# Sheet2.net
KiCad netlist of a schematic drawn in Altium Designer
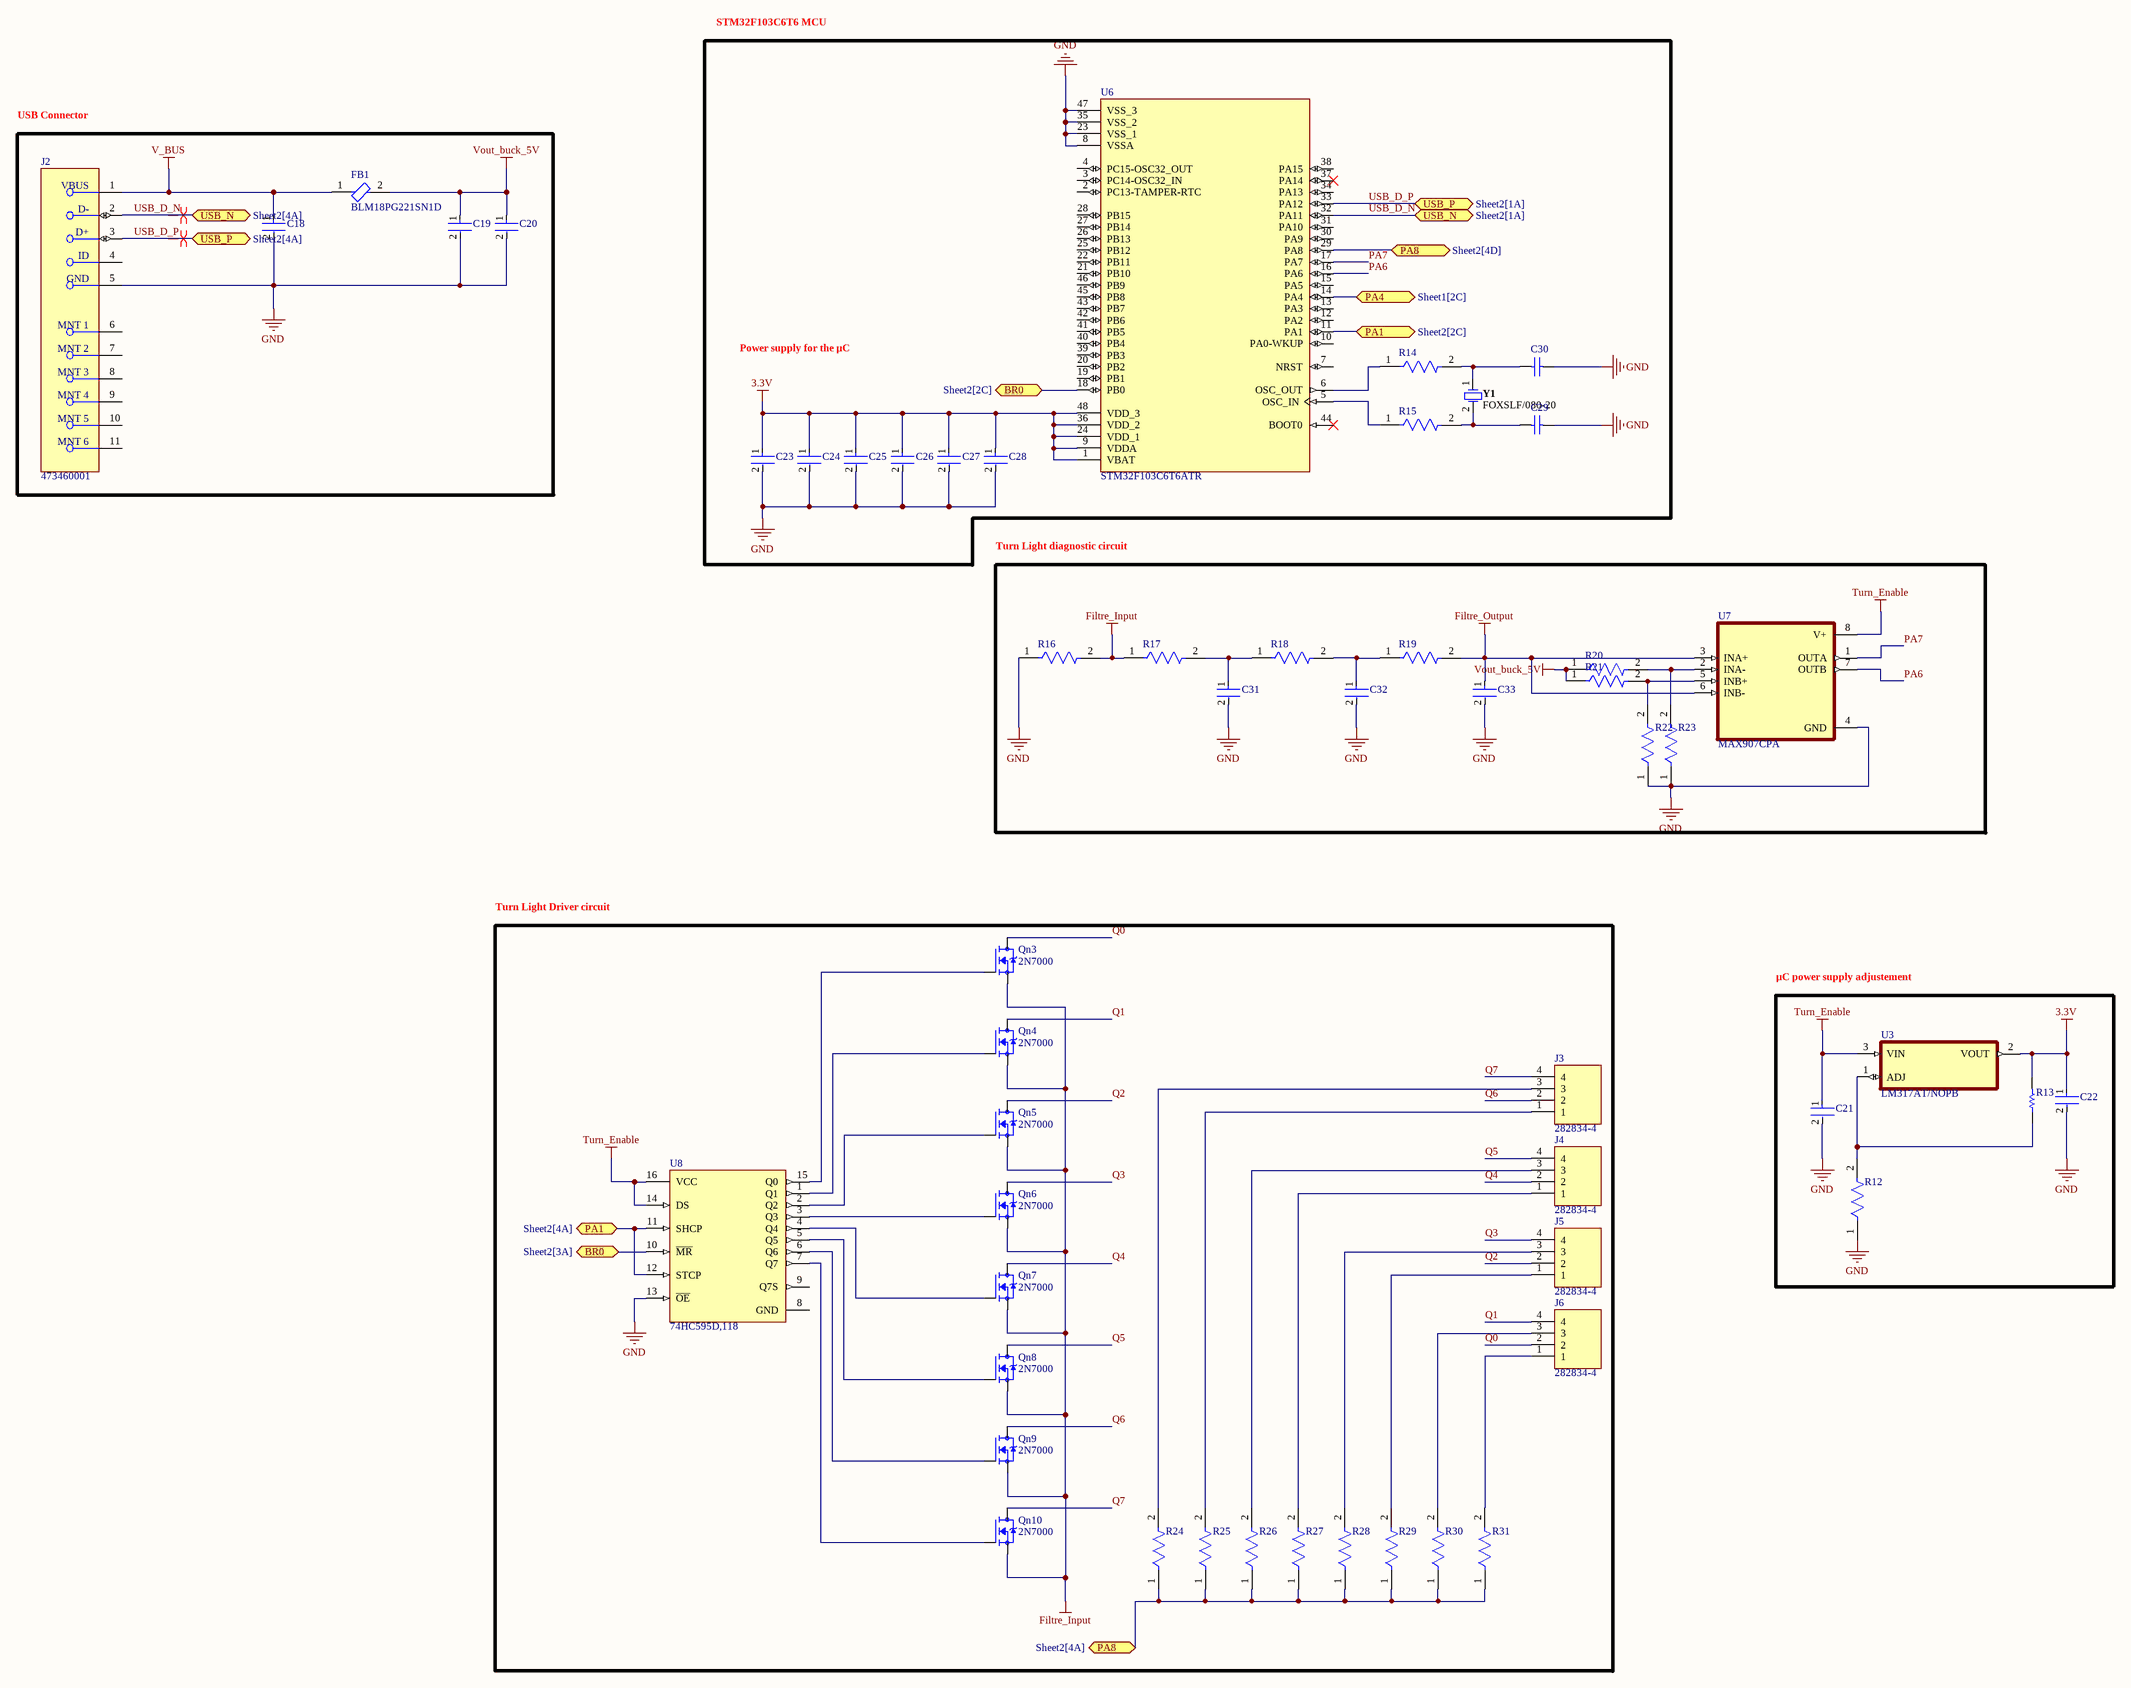
[diagram p0: Sheet2.SchDoc]

(export (version "E")
  (design (tool "Eeschema 10.0.6"))
  (components
    (comp (ref "C18")
      (value "06035C103KAT2A")
      (footprint "FP-0603-L_1_6_0_15-W_0_81-MFG")
      (description "General Purpose Ceramic Capacitor, 0603, 10nF, 10%, X7R, 15%, 50V")
      (fields (field (name "VOLTAGE") "50V") (field (name "TOLERANCE") "10%"))
      (libsource (lib "Altium Content Vault") (part "02cd4be3c70576c341d710602a673aa"))
    )
    (comp (ref "C19")
      (value "C0402C104K8PACTU")
      (footprint "FP-C0402-BB-MFG")
      (description "CAP CER 0.1UF 10V X5R 0402")
      (fields (field (name "MANUFACTURER") "Kemet") (field (name "TOLERANCE") "0.1"))
      (libsource (lib "Altium Content Vault") (part "b4654b650e69147ec39a6b967a45e02"))
    )
    (comp (ref "C20")
      (value "GRM155R60J475ME47D")
      (footprint "FP-GRM155-0_1-IPC_B")
      (description "Chip Multilayer Ceramic Capacitors for General Purpose, 0402, 4.7uF, X5R, 15%, 20%, 6.3V")
      (fields (field (name "VOLTAGE") "6.3V") (field (name "TOLERANCE") "20%"))
      (libsource (lib "Altium Content Vault") (part "11868f565c42a9108669ba33697ecf6"))
    )
    (comp (ref "C21")
      (value "CGA2B3X7R1H104M050BB")
      (footprint "FP-CGA2B-MFG")
      (description "Cap Ceramic 100nF 50V X7R 20% Pad SMD 0402 +125°C Automotive T/R")
      (fields (field (name "TOLERANCE") "20%"))
      (libsource (lib "Altium Content Vault") (part "b4654b650e69147ec39a6b967a45e02"))
    )
    (comp (ref "C22")
      (value "C0603C105K3PACTU")
      (footprint "FP-C0603C105K3PACTU-MFG")
      (description "CAP CER 1UF 25V X5R 0603")
      (fields (field (name "VOLTAGE") "25V") (field (name "TOLERANCE") "10%"))
      (libsource (lib "Altium Content Vault") (part "e9c51b7dd13d4faca003ae77663ab08"))
    )
    (comp (ref "C23")
      (value "GRM188R71A225KE15D")
      (footprint "FP-GRM188-0_1-e0_2_0_5-MFG")
      (description "Chip Multilayer Ceramic Capacitors for General Purpose, 0603, 2.2uF, X7R, 15%, 10%, 10V")
      (fields (field (name "VOLTAGE") "10V") (field (name "TOLERANCE") "10%"))
      (libsource (lib "Altium Content Vault") (part "11868f565c42a9108669ba33697ecf6"))
    )
    (comp (ref "C24")
      (value "C0402C104K8PACTU")
      (footprint "FP-C0402-BB-MFG")
      (description "CAP CER 0.1UF 10V X5R 0402")
      (fields (field (name "MANUFACTURER") "Kemet") (field (name "TOLERANCE") "0.1"))
      (libsource (lib "Altium Content Vault") (part "b4654b650e69147ec39a6b967a45e02"))
    )
    (comp (ref "C25")
      (value "C0402C104K8PACTU")
      (footprint "FP-C0402-BB-MFG")
      (description "CAP CER 0.1UF 10V X5R 0402")
      (fields (field (name "MANUFACTURER") "Kemet") (field (name "TOLERANCE") "0.1"))
      (libsource (lib "Altium Content Vault") (part "b4654b650e69147ec39a6b967a45e02"))
    )
    (comp (ref "C26")
      (value "C0402C104K8PACTU")
      (footprint "FP-C0402-BB-MFG")
      (description "CAP CER 0.1UF 10V X5R 0402")
      (fields (field (name "MANUFACTURER") "Kemet") (field (name "TOLERANCE") "0.1"))
      (libsource (lib "Altium Content Vault") (part "b4654b650e69147ec39a6b967a45e02"))
    )
    (comp (ref "C27")
      (value "C0402C104K8PACTU")
      (footprint "FP-C0402-BB-MFG")
      (description "CAP CER 0.1UF 10V X5R 0402")
      (fields (field (name "MANUFACTURER") "Kemet") (field (name "TOLERANCE") "0.1"))
      (libsource (lib "Altium Content Vault") (part "b4654b650e69147ec39a6b967a45e02"))
    )
    (comp (ref "C28")
      (value "C0402C104K8PACTU")
      (footprint "FP-C0402-BB-MFG")
      (description "CAP CER 0.1UF 10V X5R 0402")
      (fields (field (name "MANUFACTURER") "Kemet") (field (name "TOLERANCE") "0.1"))
      (libsource (lib "Altium Content Vault") (part "b4654b650e69147ec39a6b967a45e02"))
    )
    (comp (ref "C29")
      (value "C1608C0G1H220J080AA")
      (footprint "FP-C1608-080-0_1-IPC_B")
      (fields (field (name "PART NUMBER") "GRM1555C1H220JZ01D") (field (name "MANUFACTURER") "Murata"))
      (libsource (lib "Altium Content Vault") (part "CAP"))
    )
    (comp (ref "C30")
      (value "08052U220GAT2A")
      (footprint "CAPC2013X115X51NL20T26")
      (fields (field (name "PART NUMBER") "GRM1555C1H220JZ01D") (field (name "MANUFACTURER") "Murata"))
      (libsource (lib "Altium Content Vault") (part "CAP"))
    )
    (comp (ref "C31")
      (value "GRM188R60J106ME47D")
      (footprint "FP-GRM188-0_1-e0_2_0_55-IPC_A")
      (description "Chip Multilayer Ceramic Capacitors for General Purpose, 0603, 10uF, X5R, 15%, 20%, 6.3V")
      (fields (field (name "VOLTAGE") "6.3V") (field (name "TOLERANCE") "20%"))
      (libsource (lib "Altium Content Vault") (part "02cd4be3c70576c341d710602a673aa"))
    )
    (comp (ref "C32")
      (value "GRM188R60J106ME47D")
      (footprint "FP-GRM188-0_1-e0_2_0_55-IPC_A")
      (description "Chip Multilayer Ceramic Capacitors for General Purpose, 0603, 10uF, X5R, 15%, 20%, 6.3V")
      (fields (field (name "VOLTAGE") "6.3V") (field (name "TOLERANCE") "20%"))
      (libsource (lib "Altium Content Vault") (part "02cd4be3c70576c341d710602a673aa"))
    )
    (comp (ref "C33")
      (value "GRM188R60J106ME47D")
      (footprint "FP-GRM188-0_1-e0_2_0_55-IPC_A")
      (description "Chip Multilayer Ceramic Capacitors for General Purpose, 0603, 10uF, X5R, 15%, 20%, 6.3V")
      (fields (field (name "VOLTAGE") "6.3V") (field (name "TOLERANCE") "20%"))
      (libsource (lib "Altium Content Vault") (part "02cd4be3c70576c341d710602a673aa"))
    )
    (comp (ref "FB1")
      (value "BLM18PG221SN1D")
      (footprint "FP-BLM18-0_15-t0_8-IPC_B")
      (description "Chip Ferrite Bead, 0603, 220Ω @ 100MHz, 0.1Ω, 25%, 1.4A")
      (fields (field (name "TOLERANCE") "25%"))
      (libsource (lib "Altium Content Vault") (part "5f30dd21d616792df468990f7003faa"))
    )
    (comp (ref "J2")
      (value "473460001")
      (footprint "FP-473460001-MFG")
      (description "CONN RCPT USB2.0 MICRO B SMD R/A")
      (fields
        (field (name "OCTOPART") "https://octopart.com/47346-0001-molex-7164928")
        (field (name "MANUFACTURER") "Molex")
      )
      (libsource (lib "Altium Content Vault") (part "53ae1f1d9b557310b43ca686e5bb76a"))
    )
    (comp (ref "J3")
      (value "282834-4")
      (footprint "TE_282834-4")
      (description "4 Position Wire to Board Terminal Block Horizontal with Board 0.100 (2.54mm) Through Hole")
      (fields (field (name "MF") "TE Connectivity"))
      (libsource (lib "282834-4") (part "282834-4"))
    )
    (comp (ref "J4")
      (value "282834-4")
      (footprint "TE_282834-4")
      (description "4 Position Wire to Board Terminal Block Horizontal with Board 0.100 (2.54mm) Through Hole")
      (fields (field (name "MF") "TE Connectivity"))
      (libsource (lib "282834-4") (part "282834-4"))
    )
    (comp (ref "J5")
      (value "282834-4")
      (footprint "TE_282834-4")
      (description "4 Position Wire to Board Terminal Block Horizontal with Board 0.100 (2.54mm) Through Hole")
      (fields (field (name "MF") "TE Connectivity"))
      (libsource (lib "282834-4") (part "282834-4"))
    )
    (comp (ref "J6")
      (value "282834-4")
      (footprint "TE_282834-4")
      (description "4 Position Wire to Board Terminal Block Horizontal with Board 0.100 (2.54mm) Through Hole")
      (fields (field (name "MF") "TE Connectivity"))
      (libsource (lib "282834-4") (part "282834-4"))
    )
    (comp (ref "Qn3")
      (value "2N7000")
      (footprint "TO92-")
      (description "N-Channel 60 V 350mA (Tc) 1W (Tc) Through Hole TO-92-3")
      (fields (field (name "MF") "STMicroelectronics"))
      (libsource (lib "2N7000") (part "2N7000"))
    )
    (comp (ref "Qn4")
      (value "2N7000")
      (footprint "TO92-")
      (description "N-Channel 60 V 350mA (Tc) 1W (Tc) Through Hole TO-92-3")
      (fields (field (name "MF") "STMicroelectronics"))
      (libsource (lib "2N7000") (part "2N7000"))
    )
    (comp (ref "Qn5")
      (value "2N7000")
      (footprint "TO92-")
      (description "N-Channel 60 V 350mA (Tc) 1W (Tc) Through Hole TO-92-3")
      (fields (field (name "MF") "STMicroelectronics"))
      (libsource (lib "2N7000") (part "2N7000"))
    )
    (comp (ref "Qn6")
      (value "2N7000")
      (footprint "TO92-")
      (description "N-Channel 60 V 350mA (Tc) 1W (Tc) Through Hole TO-92-3")
      (fields (field (name "MF") "STMicroelectronics"))
      (libsource (lib "2N7000") (part "2N7000"))
    )
    (comp (ref "Qn7")
      (value "2N7000")
      (footprint "TO92-")
      (description "N-Channel 60 V 350mA (Tc) 1W (Tc) Through Hole TO-92-3")
      (fields (field (name "MF") "STMicroelectronics"))
      (libsource (lib "2N7000") (part "2N7000"))
    )
    (comp (ref "Qn8")
      (value "2N7000")
      (footprint "TO92-")
      (description "N-Channel 60 V 350mA (Tc) 1W (Tc) Through Hole TO-92-3")
      (fields (field (name "MF") "STMicroelectronics"))
      (libsource (lib "2N7000") (part "2N7000"))
    )
    (comp (ref "Qn9")
      (value "2N7000")
      (footprint "TO92-")
      (description "N-Channel 60 V 350mA (Tc) 1W (Tc) Through Hole TO-92-3")
      (fields (field (name "MF") "STMicroelectronics"))
      (libsource (lib "2N7000") (part "2N7000"))
    )
    (comp (ref "Qn10")
      (value "2N7000")
      (footprint "TO92-")
      (description "N-Channel 60 V 350mA (Tc) 1W (Tc) Through Hole TO-92-3")
      (fields (field (name "MF") "STMicroelectronics"))
      (libsource (lib "2N7000") (part "2N7000"))
    )
    (comp (ref "R12")
      (value "CRCW0603390RFKEA")
      (footprint "FP-CRCW0603-e3-IPC_B")
      (description "RES Thick Film, 390Ω, 1%, 0.1W, 100ppm/°C, 0603")
      (fields (field (name "TOLERANCE") "1%"))
      (libsource (lib "Altium Content Vault") (part "1029c3af85768c4190bb7ad29bc67b5"))
    )
    (comp (ref "R13")
      (value "CRCW0402240RFKED")
      (footprint "RESC1005X40X25ML05T05")
      (fields (field (name "MANUFACTURER") "Vishay Dale"))
      (libsource (lib "Altium Content Vault") (part "RES"))
    )
    (comp (ref "R14")
      (value "RCS06030000Z0EA")
      (footprint "FP-RCS0603-e3-MFG")
      (description "RES SMD 0 OHM JUMPER 1/4W 0603")
      (libsource (lib "Altium Content Vault") (part "1029c3af85768c4190bb7ad29bc67b5"))
    )
    (comp (ref "R15")
      (value "RCS06030000Z0EA")
      (footprint "FP-RCS0603-e3-MFG")
      (description "RES SMD 0 OHM JUMPER 1/4W 0603")
      (libsource (lib "Altium Content Vault") (part "1029c3af85768c4190bb7ad29bc67b5"))
    )
    (comp (ref "R16")
      (value "ERJ-2RKF10R0X")
      (footprint "FP-ERJ2RK-MFG")
      (description "RES SMD 10 OHM 1% 1/10W 0402")
      (fields
        (field (name "OCTOPART") "https://octopart.com/erj-2rkf10r0x-panasonic-55404982")
        (field (name "MANUFACTURER") "Panasonic")
      )
      (libsource (lib "Altium Content Vault") (part "1029c3af85768c4190bb7ad29bc67b5"))
    )
    (comp (ref "R17")
      (value "ERA-3AEB102V")
      (footprint "FP-ERA3A-IPC_C")
      (description "RES SMD 1K OHM 0.1% 1/10W 0603")
      (fields (field (name "TOLERANCE") "0.1%"))
      (libsource (lib "Altium Content Vault") (part "1029c3af85768c4190bb7ad29bc67b5"))
    )
    (comp (ref "R18")
      (value "ERA-3AEB102V")
      (footprint "FP-ERA3A-IPC_C")
      (description "RES SMD 1K OHM 0.1% 1/10W 0603")
      (fields (field (name "TOLERANCE") "0.1%"))
      (libsource (lib "Altium Content Vault") (part "1029c3af85768c4190bb7ad29bc67b5"))
    )
    (comp (ref "R19")
      (value "ERA-3AEB102V")
      (footprint "FP-ERA3A-IPC_C")
      (description "RES SMD 1K OHM 0.1% 1/10W 0603")
      (fields (field (name "TOLERANCE") "0.1%"))
      (libsource (lib "Altium Content Vault") (part "1029c3af85768c4190bb7ad29bc67b5"))
    )
    (comp (ref "R20")
      (value "ERA-3AEB102V")
      (footprint "FP-ERA3A-IPC_C")
      (description "RES SMD 1K OHM 0.1% 1/10W 0603")
      (fields (field (name "TOLERANCE") "0.1%"))
      (libsource (lib "Altium Content Vault") (part "1029c3af85768c4190bb7ad29bc67b5"))
    )
    (comp (ref "R21")
      (value "ERA-3AEB102V")
      (footprint "FP-ERA3A-IPC_C")
      (description "RES SMD 1K OHM 0.1% 1/10W 0603")
      (fields (field (name "TOLERANCE") "0.1%"))
      (libsource (lib "Altium Content Vault") (part "1029c3af85768c4190bb7ad29bc67b5"))
    )
    (comp (ref "R22")
      (value "CRCW060350R0FKEA")
      (footprint "FP-CRCW0603-e3-MFG")
      (description "RES Thick Film, 50Ω, 1%, 0.1W, 100ppm/°C, 0603")
      (fields (field (name "TOLERANCE") "1%"))
      (libsource (lib "Altium Content Vault") (part "1029c3af85768c4190bb7ad29bc67b5"))
    )
    (comp (ref "R23")
      (value "CRCW0402110RFKED")
      (footprint "FP-CRCW0402-e3-IPC_A")
      (description "RES Thick Film, 110Ω, 1%, 0.063W, 100ppm/°C, 0402")
      (fields (field (name "TOLERANCE") "1%"))
      (libsource (lib "Altium Content Vault") (part "1029c3af85768c4190bb7ad29bc67b5"))
    )
    (comp (ref "R24")
      (value "CRCW060350R0FKEA")
      (footprint "FP-CRCW0603-e3-MFG")
      (description "RES Thick Film, 50Ω, 1%, 0.1W, 100ppm/°C, 0603")
      (fields (field (name "TOLERANCE") "1%"))
      (libsource (lib "Altium Content Vault") (part "1029c3af85768c4190bb7ad29bc67b5"))
    )
    (comp (ref "R25")
      (value "CRCW060350R0FKEA")
      (footprint "FP-CRCW0603-e3-MFG")
      (description "RES Thick Film, 50Ω, 1%, 0.1W, 100ppm/°C, 0603")
      (fields (field (name "TOLERANCE") "1%"))
      (libsource (lib "Altium Content Vault") (part "1029c3af85768c4190bb7ad29bc67b5"))
    )
    (comp (ref "R26")
      (value "CRCW060350R0FKEA")
      (footprint "FP-CRCW0603-e3-MFG")
      (description "RES Thick Film, 50Ω, 1%, 0.1W, 100ppm/°C, 0603")
      (fields (field (name "TOLERANCE") "1%"))
      (libsource (lib "Altium Content Vault") (part "1029c3af85768c4190bb7ad29bc67b5"))
    )
    (comp (ref "R27")
      (value "CRCW060350R0FKEA")
      (footprint "FP-CRCW0603-e3-MFG")
      (description "RES Thick Film, 50Ω, 1%, 0.1W, 100ppm/°C, 0603")
      (fields (field (name "TOLERANCE") "1%"))
      (libsource (lib "Altium Content Vault") (part "1029c3af85768c4190bb7ad29bc67b5"))
    )
    (comp (ref "R28")
      (value "CRCW060350R0FKEA")
      (footprint "FP-CRCW0603-e3-MFG")
      (description "RES Thick Film, 50Ω, 1%, 0.1W, 100ppm/°C, 0603")
      (fields (field (name "TOLERANCE") "1%"))
      (libsource (lib "Altium Content Vault") (part "1029c3af85768c4190bb7ad29bc67b5"))
    )
    (comp (ref "R29")
      (value "CRCW060350R0FKEA")
      (footprint "FP-CRCW0603-e3-MFG")
      (description "RES Thick Film, 50Ω, 1%, 0.1W, 100ppm/°C, 0603")
      (fields (field (name "TOLERANCE") "1%"))
      (libsource (lib "Altium Content Vault") (part "1029c3af85768c4190bb7ad29bc67b5"))
    )
    (comp (ref "R30")
      (value "CRCW060350R0FKEA")
      (footprint "FP-CRCW0603-e3-MFG")
      (description "RES Thick Film, 50Ω, 1%, 0.1W, 100ppm/°C, 0603")
      (fields (field (name "TOLERANCE") "1%"))
      (libsource (lib "Altium Content Vault") (part "1029c3af85768c4190bb7ad29bc67b5"))
    )
    (comp (ref "R31")
      (value "CRCW060350R0FKEA")
      (footprint "FP-CRCW0603-e3-MFG")
      (description "RES Thick Film, 50Ω, 1%, 0.1W, 100ppm/°C, 0603")
      (fields (field (name "TOLERANCE") "1%"))
      (libsource (lib "Altium Content Vault") (part "1029c3af85768c4190bb7ad29bc67b5"))
    )
    (comp (ref "U3")
      (value "LM317AT/NOPB")
      (footprint "TO254P1054X470X1955-3")
      (description "1.5-A, 40-V, adjustable linear voltage regulator with high-accuracy 3-TO-220 -40 to 125")
      (fields (field (name "MP") "LM317AT") (field (name "MF") "Texas Instruments"))
      (libsource (lib "LM317AT_NOPB") (part "LM317AT/NOPB"))
    )
    (comp (ref "U6")
      (value "STM32F103C6T6ATR")
      (footprint "QFP50P900X900X160-48N")
      (description "ARMÂ® CortexÂ®-M3 STM32F1 Microcontroller IC 32-Bit 72MHz 32KB (32K x 8) FLASH")
      (fields (field (name "MF") "STMicroelectronics"))
      (libsource (lib "STM32F103C6T6ATR") (part "STM32F103C6T6ATR"))
    )
    (comp (ref "U7")
      (value "MAX907CPA")
      (footprint "DIP794W47P254L991H457Q8")
      (description "Comparator General Purpose TTL 8-PDIP")
      (fields (field (name "MF") "Maxim Integrated"))
      (libsource (lib "MAX907CPA") (part "MAX907CPA"))
    )
    (comp (ref "U8")
      (value "74HC595D,118")
      (footprint "FP-SOT109-1-IPC_C")
      (description "IC SHIFT REGISTER 8BIT 16SOIC")
      (libsource (lib "Altium Content Vault") (part "7b153f231cfcc3ac06dee253bd56617"))
    )
    (comp (ref "Y1")
      (value "FOXSLF/080-20")
      (footprint "FOX-FOXSLF080-20")
      (description "Resistance Weld Thru-Hole Crystal, 8 MHz, -20 to 70 degC, 2-Pin THD, RoHS, Bulk")
      (libsource (lib "Altium Content Vault") (part "XTAL-1-2-2"))
    )
  )
  (nets
    (net (code "1") (name "/BR0") (class "Default")
      (node (ref "U6") (pin "18") (pinfunction "PB0_18") (pintype "bidirectional"))
      (node (ref "U8") (pin "10") (pinfunction "~{MR}_10") (pintype "input"))
    )
    (net (code "2") (name "/PA1") (class "Default")
      (node (ref "U6") (pin "11") (pinfunction "PA1_11") (pintype "bidirectional"))
      (node (ref "U8") (pin "11") (pinfunction "SHCP_11") (pintype "input"))
      (node (ref "U8") (pin "12") (pinfunction "STCP_12") (pintype "input"))
    )
    (net (code "3") (name "/PA4") (class "Default")
      (node (ref "U6") (pin "14") (pinfunction "PA4_14") (pintype "bidirectional"))
    )
    (net (code "4") (name "/PA6") (class "Default")
      (node (ref "U6") (pin "16") (pinfunction "PA6_16") (pintype "bidirectional"))
      (node (ref "U7") (pin "7") (pinfunction "OUTB_7") (pintype "output"))
    )
    (net (code "5") (name "/PA7") (class "Default")
      (node (ref "U6") (pin "17") (pinfunction "PA7_17") (pintype "bidirectional"))
      (node (ref "U7") (pin "1") (pinfunction "OUTA_1") (pintype "output"))
    )
    (net (code "6") (name "/PA8") (class "Default")
      (node (ref "R24") (pin "1") (pinfunction "1_1") (pintype "passive"))
      (node (ref "R25") (pin "1") (pinfunction "1_1") (pintype "passive"))
      (node (ref "R26") (pin "1") (pinfunction "1_1") (pintype "passive"))
      (node (ref "R27") (pin "1") (pinfunction "1_1") (pintype "passive"))
      (node (ref "R28") (pin "1") (pinfunction "1_1") (pintype "passive"))
      (node (ref "R29") (pin "1") (pinfunction "1_1") (pintype "passive"))
      (node (ref "R30") (pin "1") (pinfunction "1_1") (pintype "passive"))
      (node (ref "R31") (pin "1") (pinfunction "1_1") (pintype "passive"))
      (node (ref "U6") (pin "29") (pinfunction "PA8_29") (pintype "bidirectional"))
    )
    (net (code "7") (name "/Q0") (class "Default")
      (node (ref "J6") (pin "2") (pinfunction "2_2") (pintype "passive"))
      (node (ref "Qn3") (pin "1") (pinfunction "D_1") (pintype "passive"))
    )
    (net (code "8") (name "/Q1") (class "Default")
      (node (ref "J6") (pin "4") (pinfunction "4_4") (pintype "passive"))
      (node (ref "Qn4") (pin "1") (pinfunction "D_1") (pintype "passive"))
    )
    (net (code "9") (name "/Q2") (class "Default")
      (node (ref "J5") (pin "2") (pinfunction "2_2") (pintype "passive"))
      (node (ref "Qn5") (pin "1") (pinfunction "D_1") (pintype "passive"))
    )
    (net (code "10") (name "/Q3") (class "Default")
      (node (ref "J5") (pin "4") (pinfunction "4_4") (pintype "passive"))
      (node (ref "Qn6") (pin "1") (pinfunction "D_1") (pintype "passive"))
    )
    (net (code "11") (name "/Q4") (class "Default")
      (node (ref "J4") (pin "2") (pinfunction "2_2") (pintype "passive"))
      (node (ref "Qn7") (pin "1") (pinfunction "D_1") (pintype "passive"))
    )
    (net (code "12") (name "/Q5") (class "Default")
      (node (ref "J4") (pin "4") (pinfunction "4_4") (pintype "passive"))
      (node (ref "Qn8") (pin "1") (pinfunction "D_1") (pintype "passive"))
    )
    (net (code "13") (name "/Q6") (class "Default")
      (node (ref "J3") (pin "2") (pinfunction "2_2") (pintype "passive"))
      (node (ref "Qn9") (pin "1") (pinfunction "D_1") (pintype "passive"))
    )
    (net (code "14") (name "/Q7") (class "Default")
      (node (ref "J3") (pin "4") (pinfunction "4_4") (pintype "passive"))
      (node (ref "Qn10") (pin "1") (pinfunction "D_1") (pintype "passive"))
    )
    (net (code "15") (name "/USB_D_N") (class "Default")
      (node (ref "J2") (pin "2") (pinfunction "D-_2") (pintype "bidirectional"))
      (node (ref "U6") (pin "32") (pinfunction "PA11_32") (pintype "bidirectional"))
    )
    (net (code "16") (name "/USB_D_P") (class "Default")
      (node (ref "J2") (pin "3") (pinfunction "D+_3") (pintype "bidirectional"))
      (node (ref "U6") (pin "33") (pinfunction "PA12_33") (pintype "bidirectional"))
    )
    (net (code "17") (name "3.3V") (class "Default")
      (node (ref "C22") (pin "1") (pinfunction "1_1") (pintype "passive"))
      (node (ref "C23") (pin "1") (pinfunction "1_1") (pintype "passive"))
      (node (ref "C24") (pin "1") (pinfunction "1_1") (pintype "passive"))
      (node (ref "C25") (pin "1") (pinfunction "1_1") (pintype "passive"))
      (node (ref "C26") (pin "1") (pinfunction "1_1") (pintype "passive"))
      (node (ref "C27") (pin "1") (pinfunction "1_1") (pintype "passive"))
      (node (ref "C28") (pin "1") (pinfunction "1_1") (pintype "passive"))
      (node (ref "R13") (pin "2") (pinfunction "2_2") (pintype "passive"))
      (node (ref "U3") (pin "2") (pinfunction "VOUT_2") (pintype "output"))
      (node (ref "U6") (pin "1") (pinfunction "VBAT_1") (pintype "power_in"))
      (node (ref "U6") (pin "24") (pinfunction "VDD_1_24") (pintype "power_in"))
      (node (ref "U6") (pin "36") (pinfunction "VDD_2_36") (pintype "power_in"))
      (node (ref "U6") (pin "48") (pinfunction "VDD_3_48") (pintype "power_in"))
      (node (ref "U6") (pin "9") (pinfunction "VDDA_9") (pintype "power_in"))
    )
    (net (code "18") (name "Filtre_Input") (class "Default")
      (node (ref "Qn10") (pin "3") (pinfunction "S_3") (pintype "passive"))
      (node (ref "Qn3") (pin "3") (pinfunction "S_3") (pintype "passive"))
      (node (ref "Qn4") (pin "3") (pinfunction "S_3") (pintype "passive"))
      (node (ref "Qn5") (pin "3") (pinfunction "S_3") (pintype "passive"))
      (node (ref "Qn6") (pin "3") (pinfunction "S_3") (pintype "passive"))
      (node (ref "Qn7") (pin "3") (pinfunction "S_3") (pintype "passive"))
      (node (ref "Qn8") (pin "3") (pinfunction "S_3") (pintype "passive"))
      (node (ref "Qn9") (pin "3") (pinfunction "S_3") (pintype "passive"))
      (node (ref "R16") (pin "2") (pinfunction "2_2") (pintype "passive"))
      (node (ref "R17") (pin "1") (pinfunction "1_1") (pintype "passive"))
    )
    (net (code "19") (name "Filtre_Output") (class "Default")
      (node (ref "C33") (pin "1") (pinfunction "1_1") (pintype "passive"))
      (node (ref "R19") (pin "2") (pinfunction "2_2") (pintype "passive"))
      (node (ref "U7") (pin "3") (pinfunction "INA+_3") (pintype "input"))
      (node (ref "U7") (pin "6") (pinfunction "INB-_6") (pintype "input"))
    )
    (net (code "20") (name "GND") (class "Default")
      (node (ref "C18") (pin "2") (pinfunction "2_2") (pintype "passive"))
      (node (ref "C19") (pin "2") (pinfunction "2_2") (pintype "passive"))
      (node (ref "C20") (pin "2") (pinfunction "2_2") (pintype "passive"))
      (node (ref "C21") (pin "2") (pinfunction "2_2") (pintype "passive"))
      (node (ref "C22") (pin "2") (pinfunction "2_2") (pintype "passive"))
      (node (ref "C23") (pin "2") (pinfunction "2_2") (pintype "passive"))
      (node (ref "C24") (pin "2") (pinfunction "2_2") (pintype "passive"))
      (node (ref "C25") (pin "2") (pinfunction "2_2") (pintype "passive"))
      (node (ref "C26") (pin "2") (pinfunction "2_2") (pintype "passive"))
      (node (ref "C27") (pin "2") (pinfunction "2_2") (pintype "passive"))
      (node (ref "C28") (pin "2") (pinfunction "2_2") (pintype "passive"))
      (node (ref "C29") (pin "1") (pinfunction "1_1") (pintype "passive"))
      (node (ref "C30") (pin "1") (pinfunction "1_1") (pintype "passive"))
      (node (ref "C31") (pin "2") (pinfunction "2_2") (pintype "passive"))
      (node (ref "C32") (pin "2") (pinfunction "2_2") (pintype "passive"))
      (node (ref "C33") (pin "2") (pinfunction "2_2") (pintype "passive"))
      (node (ref "J2") (pin "5") (pinfunction "GND_5") (pintype "power_in"))
      (node (ref "R12") (pin "1") (pinfunction "1_1") (pintype "passive"))
      (node (ref "R16") (pin "1") (pinfunction "1_1") (pintype "passive"))
      (node (ref "R22") (pin "1") (pinfunction "1_1") (pintype "passive"))
      (node (ref "R23") (pin "1") (pinfunction "1_1") (pintype "passive"))
      (node (ref "U6") (pin "23") (pinfunction "VSS_1_23") (pintype "power_in"))
      (node (ref "U6") (pin "35") (pinfunction "VSS_2_35") (pintype "power_in"))
      (node (ref "U6") (pin "47") (pinfunction "VSS_3_47") (pintype "power_in"))
      (node (ref "U6") (pin "8") (pinfunction "VSSA_8") (pintype "power_in"))
      (node (ref "U7") (pin "4") (pinfunction "GND_4") (pintype "power_in"))
      (node (ref "U8") (pin "13") (pinfunction "~{OE}_13") (pintype "input"))
    )
    (net (code "21") (name "Net-(C29-Pad2)") (class "Default")
      (node (ref "C29") (pin "2") (pinfunction "2_2") (pintype "passive"))
      (node (ref "R15") (pin "2") (pinfunction "2_2") (pintype "passive"))
      (node (ref "Y1") (pin "2") (pinfunction "2_2") (pintype "passive"))
    )
    (net (code "22") (name "Net-(C30-Pad2)") (class "Default")
      (node (ref "C30") (pin "2") (pinfunction "2_2") (pintype "passive"))
      (node (ref "R14") (pin "2") (pinfunction "2_2") (pintype "passive"))
      (node (ref "Y1") (pin "1") (pinfunction "1_1") (pintype "passive"))
    )
    (net (code "23") (name "Net-(C31-Pad1)") (class "Default")
      (node (ref "C31") (pin "1") (pinfunction "1_1") (pintype "passive"))
      (node (ref "R17") (pin "2") (pinfunction "2_2") (pintype "passive"))
      (node (ref "R18") (pin "1") (pinfunction "1_1") (pintype "passive"))
    )
    (net (code "24") (name "Net-(C32-Pad1)") (class "Default")
      (node (ref "C32") (pin "1") (pinfunction "1_1") (pintype "passive"))
      (node (ref "R18") (pin "2") (pinfunction "2_2") (pintype "passive"))
      (node (ref "R19") (pin "1") (pinfunction "1_1") (pintype "passive"))
    )
    (net (code "25") (name "Net-(J3-Pad1)") (class "Default")
      (node (ref "J3") (pin "1") (pinfunction "1_1") (pintype "passive"))
      (node (ref "R25") (pin "2") (pinfunction "2_2") (pintype "passive"))
    )
    (net (code "26") (name "Net-(J3-Pad3)") (class "Default")
      (node (ref "J3") (pin "3") (pinfunction "3_3") (pintype "passive"))
      (node (ref "R24") (pin "2") (pinfunction "2_2") (pintype "passive"))
    )
    (net (code "27") (name "Net-(J4-Pad1)") (class "Default")
      (node (ref "J4") (pin "1") (pinfunction "1_1") (pintype "passive"))
      (node (ref "R27") (pin "2") (pinfunction "2_2") (pintype "passive"))
    )
    (net (code "28") (name "Net-(J4-Pad3)") (class "Default")
      (node (ref "J4") (pin "3") (pinfunction "3_3") (pintype "passive"))
      (node (ref "R26") (pin "2") (pinfunction "2_2") (pintype "passive"))
    )
    (net (code "29") (name "Net-(J5-Pad1)") (class "Default")
      (node (ref "J5") (pin "1") (pinfunction "1_1") (pintype "passive"))
      (node (ref "R29") (pin "2") (pinfunction "2_2") (pintype "passive"))
    )
    (net (code "30") (name "Net-(J5-Pad3)") (class "Default")
      (node (ref "J5") (pin "3") (pinfunction "3_3") (pintype "passive"))
      (node (ref "R28") (pin "2") (pinfunction "2_2") (pintype "passive"))
    )
    (net (code "31") (name "Net-(J6-Pad1)") (class "Default")
      (node (ref "J6") (pin "1") (pinfunction "1_1") (pintype "passive"))
      (node (ref "R31") (pin "2") (pinfunction "2_2") (pintype "passive"))
    )
    (net (code "32") (name "Net-(J6-Pad3)") (class "Default")
      (node (ref "J6") (pin "3") (pinfunction "3_3") (pintype "passive"))
      (node (ref "R30") (pin "2") (pinfunction "2_2") (pintype "passive"))
    )
    (net (code "33") (name "Net-(Qn3-G)") (class "Default")
      (node (ref "Qn3") (pin "2") (pinfunction "G_2") (pintype "passive"))
      (node (ref "U8") (pin "15") (pinfunction "Q0_15") (pintype "output"))
    )
    (net (code "34") (name "Net-(Qn4-G)") (class "Default")
      (node (ref "Qn4") (pin "2") (pinfunction "G_2") (pintype "passive"))
      (node (ref "U8") (pin "1") (pinfunction "Q1_1") (pintype "output"))
    )
    (net (code "35") (name "Net-(Qn5-G)") (class "Default")
      (node (ref "Qn5") (pin "2") (pinfunction "G_2") (pintype "passive"))
      (node (ref "U8") (pin "2") (pinfunction "Q2_2") (pintype "output"))
    )
    (net (code "36") (name "Net-(Qn6-G)") (class "Default")
      (node (ref "Qn6") (pin "2") (pinfunction "G_2") (pintype "passive"))
      (node (ref "U8") (pin "3") (pinfunction "Q3_3") (pintype "output"))
    )
    (net (code "37") (name "Net-(Qn7-G)") (class "Default")
      (node (ref "Qn7") (pin "2") (pinfunction "G_2") (pintype "passive"))
      (node (ref "U8") (pin "4") (pinfunction "Q4_4") (pintype "output"))
    )
    (net (code "38") (name "Net-(Qn8-G)") (class "Default")
      (node (ref "Qn8") (pin "2") (pinfunction "G_2") (pintype "passive"))
      (node (ref "U8") (pin "5") (pinfunction "Q5_5") (pintype "output"))
    )
    (net (code "39") (name "Net-(Qn9-G)") (class "Default")
      (node (ref "Qn9") (pin "2") (pinfunction "G_2") (pintype "passive"))
      (node (ref "U8") (pin "6") (pinfunction "Q6_6") (pintype "output"))
    )
    (net (code "40") (name "Net-(Qn10-G)") (class "Default")
      (node (ref "Qn10") (pin "2") (pinfunction "G_2") (pintype "passive"))
      (node (ref "U8") (pin "7") (pinfunction "Q7_7") (pintype "output"))
    )
    (net (code "41") (name "Net-(U3-ADJ)") (class "Default")
      (node (ref "R12") (pin "2") (pinfunction "2_2") (pintype "passive"))
      (node (ref "R13") (pin "1") (pinfunction "1_1") (pintype "passive"))
      (node (ref "U3") (pin "1") (pinfunction "ADJ_1") (pintype "bidirectional"))
    )
    (net (code "42") (name "Net-(U6-OSC_IN)") (class "Default")
      (node (ref "R15") (pin "1") (pinfunction "1_1") (pintype "passive"))
      (node (ref "U6") (pin "5") (pinfunction "OSC_IN_5") (pintype "input"))
    )
    (net (code "43") (name "Net-(U6-OSC_OUT)") (class "Default")
      (node (ref "R14") (pin "1") (pinfunction "1_1") (pintype "passive"))
      (node (ref "U6") (pin "6") (pinfunction "OSC_OUT_6") (pintype "output"))
    )
    (net (code "44") (name "Net-(U7-INA-)") (class "Default")
      (node (ref "R20") (pin "2") (pinfunction "2_2") (pintype "passive"))
      (node (ref "R23") (pin "2") (pinfunction "2_2") (pintype "passive"))
      (node (ref "U7") (pin "2") (pinfunction "INA-_2") (pintype "input"))
    )
    (net (code "45") (name "Net-(U7-INB+)") (class "Default")
      (node (ref "R21") (pin "2") (pinfunction "2_2") (pintype "passive"))
      (node (ref "R22") (pin "2") (pinfunction "2_2") (pintype "passive"))
      (node (ref "U7") (pin "5") (pinfunction "INB+_5") (pintype "input"))
    )
    (net (code "46") (name "Turn_Enable") (class "Default")
      (node (ref "C21") (pin "1") (pinfunction "1_1") (pintype "passive"))
      (node (ref "U3") (pin "3") (pinfunction "VIN_3") (pintype "input"))
      (node (ref "U7") (pin "8") (pinfunction "V+_8") (pintype "power_in"))
      (node (ref "U8") (pin "14") (pinfunction "DS_14") (pintype "input"))
      (node (ref "U8") (pin "16") (pinfunction "VCC_16") (pintype "power_in"))
    )
    (net (code "47") (name "V_BUS") (class "Default")
      (node (ref "C18") (pin "1") (pinfunction "1_1") (pintype "passive"))
      (node (ref "FB1") (pin "1") (pinfunction "1_1") (pintype "passive"))
      (node (ref "J2") (pin "1") (pinfunction "VBUS_1") (pintype "power_in"))
    )
    (net (code "48") (name "Vout_buck_5V") (class "Default")
      (node (ref "C19") (pin "1") (pinfunction "1_1") (pintype "passive"))
      (node (ref "C20") (pin "1") (pinfunction "1_1") (pintype "passive"))
      (node (ref "FB1") (pin "2") (pinfunction "2_2") (pintype "passive"))
      (node (ref "R20") (pin "1") (pinfunction "1_1") (pintype "passive"))
      (node (ref "R21") (pin "1") (pinfunction "1_1") (pintype "passive"))
    )
    (net (code "49") (name "unconnected-(J2-ID-Pad4)") (class "Default")
      (node (ref "J2") (pin "4") (pinfunction "ID_4") (pintype "passive"))
    )
    (net (code "50") (name "unconnected-(J2-MNT_1-Pad6)") (class "Default")
      (node (ref "J2") (pin "6") (pinfunction "MNT_1_6") (pintype "passive"))
    )
    (net (code "51") (name "unconnected-(J2-MNT_2-Pad7)") (class "Default")
      (node (ref "J2") (pin "7") (pinfunction "MNT_2_7") (pintype "passive"))
    )
    (net (code "52") (name "unconnected-(J2-MNT_3-Pad8)") (class "Default")
      (node (ref "J2") (pin "8") (pinfunction "MNT_3_8") (pintype "passive"))
    )
    (net (code "53") (name "unconnected-(J2-MNT_4-Pad9)") (class "Default")
      (node (ref "J2") (pin "9") (pinfunction "MNT_4_9") (pintype "passive"))
    )
    (net (code "54") (name "unconnected-(J2-MNT_5-Pad10)") (class "Default")
      (node (ref "J2") (pin "10") (pinfunction "MNT_5_10") (pintype "passive"))
    )
    (net (code "55") (name "unconnected-(J2-MNT_6-Pad11)") (class "Default")
      (node (ref "J2") (pin "11") (pinfunction "MNT_6_11") (pintype "passive"))
    )
    (net (code "56") (name "unconnected-(U6-BOOT0-Pad44)") (class "Default")
      (node (ref "U6") (pin "44") (pinfunction "BOOT0_44") (pintype "input+no_connect"))
    )
    (net (code "57") (name "unconnected-(U6-NRST-Pad7)") (class "Default")
      (node (ref "U6") (pin "7") (pinfunction "NRST_7") (pintype "bidirectional"))
    )
    (net (code "58") (name "unconnected-(U6-PA0-WKUP-Pad10)") (class "Default")
      (node (ref "U6") (pin "10") (pinfunction "PA0-WKUP_10") (pintype "bidirectional"))
    )
    (net (code "59") (name "unconnected-(U6-PA2-Pad12)") (class "Default")
      (node (ref "U6") (pin "12") (pinfunction "PA2_12") (pintype "bidirectional"))
    )
    (net (code "60") (name "unconnected-(U6-PA3-Pad13)") (class "Default")
      (node (ref "U6") (pin "13") (pinfunction "PA3_13") (pintype "bidirectional"))
    )
    (net (code "61") (name "unconnected-(U6-PA5-Pad15)") (class "Default")
      (node (ref "U6") (pin "15") (pinfunction "PA5_15") (pintype "bidirectional"))
    )
    (net (code "62") (name "unconnected-(U6-PA9-Pad30)") (class "Default")
      (node (ref "U6") (pin "30") (pinfunction "PA9_30") (pintype "bidirectional"))
    )
    (net (code "63") (name "unconnected-(U6-PA10-Pad31)") (class "Default")
      (node (ref "U6") (pin "31") (pinfunction "PA10_31") (pintype "bidirectional"))
    )
    (net (code "64") (name "unconnected-(U6-PA13-Pad34)") (class "Default")
      (node (ref "U6") (pin "34") (pinfunction "PA13_34") (pintype "bidirectional"))
    )
    (net (code "65") (name "unconnected-(U6-PA14-Pad37)") (class "Default")
      (node (ref "U6") (pin "37") (pinfunction "PA14_37") (pintype "bidirectional+no_connect"))
    )
    (net (code "66") (name "unconnected-(U6-PA15-Pad38)") (class "Default")
      (node (ref "U6") (pin "38") (pinfunction "PA15_38") (pintype "bidirectional"))
    )
    (net (code "67") (name "unconnected-(U6-PB1-Pad19)") (class "Default")
      (node (ref "U6") (pin "19") (pinfunction "PB1_19") (pintype "bidirectional"))
    )
    (net (code "68") (name "unconnected-(U6-PB2-Pad20)") (class "Default")
      (node (ref "U6") (pin "20") (pinfunction "PB2_20") (pintype "bidirectional"))
    )
    (net (code "69") (name "unconnected-(U6-PB3-Pad39)") (class "Default")
      (node (ref "U6") (pin "39") (pinfunction "PB3_39") (pintype "bidirectional"))
    )
    (net (code "70") (name "unconnected-(U6-PB4-Pad40)") (class "Default")
      (node (ref "U6") (pin "40") (pinfunction "PB4_40") (pintype "bidirectional"))
    )
    (net (code "71") (name "unconnected-(U6-PB5-Pad41)") (class "Default")
      (node (ref "U6") (pin "41") (pinfunction "PB5_41") (pintype "bidirectional"))
    )
    (net (code "72") (name "unconnected-(U6-PB6-Pad42)") (class "Default")
      (node (ref "U6") (pin "42") (pinfunction "PB6_42") (pintype "bidirectional"))
    )
    (net (code "73") (name "unconnected-(U6-PB7-Pad43)") (class "Default")
      (node (ref "U6") (pin "43") (pinfunction "PB7_43") (pintype "bidirectional"))
    )
    (net (code "74") (name "unconnected-(U6-PB8-Pad45)") (class "Default")
      (node (ref "U6") (pin "45") (pinfunction "PB8_45") (pintype "bidirectional"))
    )
    (net (code "75") (name "unconnected-(U6-PB9-Pad46)") (class "Default")
      (node (ref "U6") (pin "46") (pinfunction "PB9_46") (pintype "bidirectional"))
    )
    (net (code "76") (name "unconnected-(U6-PB10-Pad21)") (class "Default")
      (node (ref "U6") (pin "21") (pinfunction "PB10_21") (pintype "bidirectional"))
    )
    (net (code "77") (name "unconnected-(U6-PB11-Pad22)") (class "Default")
      (node (ref "U6") (pin "22") (pinfunction "PB11_22") (pintype "bidirectional"))
    )
    (net (code "78") (name "unconnected-(U6-PB12-Pad25)") (class "Default")
      (node (ref "U6") (pin "25") (pinfunction "PB12_25") (pintype "bidirectional"))
    )
    (net (code "79") (name "unconnected-(U6-PB13-Pad26)") (class "Default")
      (node (ref "U6") (pin "26") (pinfunction "PB13_26") (pintype "bidirectional"))
    )
    (net (code "80") (name "unconnected-(U6-PB14-Pad27)") (class "Default")
      (node (ref "U6") (pin "27") (pinfunction "PB14_27") (pintype "bidirectional"))
    )
    (net (code "81") (name "unconnected-(U6-PB15-Pad28)") (class "Default")
      (node (ref "U6") (pin "28") (pinfunction "PB15_28") (pintype "bidirectional"))
    )
    (net (code "82") (name "unconnected-(U6-PC13-TAMPER-RTC-Pad2)") (class "Default")
      (node (ref "U6") (pin "2") (pinfunction "PC13-TAMPER-RTC_2") (pintype "bidirectional"))
    )
    (net (code "83") (name "unconnected-(U6-PC14-OSC32_IN-Pad3)") (class "Default")
      (node (ref "U6") (pin "3") (pinfunction "PC14-OSC32_IN_3") (pintype "bidirectional"))
    )
    (net (code "84") (name "unconnected-(U6-PC15-OSC32_OUT-Pad4)") (class "Default")
      (node (ref "U6") (pin "4") (pinfunction "PC15-OSC32_OUT_4") (pintype "bidirectional"))
    )
    (net (code "85") (name "unconnected-(U8-GND-Pad8)") (class "Default")
      (node (ref "U8") (pin "8") (pinfunction "GND_8") (pintype "power_in"))
    )
    (net (code "86") (name "unconnected-(U8-Q7S-Pad9)") (class "Default")
      (node (ref "U8") (pin "9") (pinfunction "Q7S_9") (pintype "output"))
    )
  )
)
